# 3V3_board.net
KiCad netlist of a schematic drawn in Altium Designer
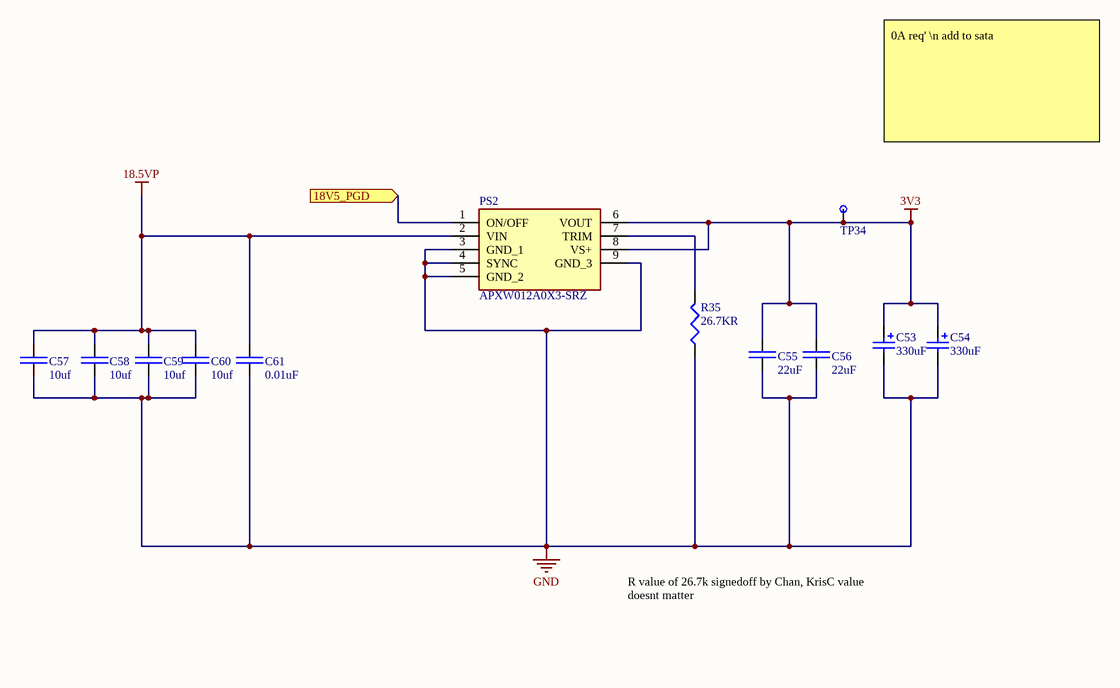
[diagram p0: 3V3_board.SchDoc]

(export (version "E")
  (design (tool "Eeschema 10.0.6"))
  (components
    (comp (ref "C53")
      (value "330uF")
      (footprint "330uF throught hole")
      (description "CAP ALUM 330UF 20% 35V RADIAL")
      (fields (field (name "TOLERANCE") "20%"))
      (libsource (lib "RSX_Capacitors") (part "35ZLH330MEFCT810X12.5"))
    )
    (comp (ref "C54")
      (value "330uF")
      (footprint "330uF throught hole")
      (description "CAP ALUM 330UF 20% 35V RADIAL")
      (fields (field (name "TOLERANCE") "20%"))
      (libsource (lib "RSX_Capacitors") (part "35ZLH330MEFCT810X12.5"))
    )
    (comp (ref "C55")
      (value "22uF")
      (footprint "22uF Capacitor")
      (description "Cap Ceramic 22uF 25V X7R 10% SMD 1210 125C Embossed T/R")
      (fields (field (name "TOLERANCE") "10%") (field (name "VOLTAGE") "25V"))
      (libsource (lib "RSX_Capacitors") (part "GRM32ER71E226KE15L"))
    )
    (comp (ref "C56")
      (value "22uF")
      (footprint "22uF Capacitor")
      (description "Cap Ceramic 22uF 25V X7R 10% SMD 1210 125C Embossed T/R")
      (fields (field (name "TOLERANCE") "10%") (field (name "VOLTAGE") "25V"))
      (libsource (lib "RSX_Capacitors") (part "GRM32ER71E226KE15L"))
    )
    (comp (ref "C57")
      (value "10uf")
      (footprint "10uF capacitor LPB")
      (description "CAP CER 10UF 50V X5R 1206")
      (fields (field (name "TOLERANCE") "20%"))
      (libsource (lib "RSX_Capacitors") (part "GRT31CR61H106ME01L"))
    )
    (comp (ref "C58")
      (value "10uf")
      (footprint "10uF capacitor LPB")
      (description "CAP CER 10UF 50V X5R 1206")
      (fields (field (name "TOLERANCE") "20%"))
      (libsource (lib "RSX_Capacitors") (part "GRT31CR61H106ME01L"))
    )
    (comp (ref "C59")
      (value "10uf")
      (footprint "10uF capacitor LPB")
      (description "CAP CER 10UF 50V X5R 1206")
      (fields (field (name "TOLERANCE") "20%"))
      (libsource (lib "RSX_Capacitors") (part "GRT31CR61H106ME01L"))
    )
    (comp (ref "C60")
      (value "10uf")
      (footprint "10uF capacitor LPB")
      (description "CAP CER 10UF 50V X5R 1206")
      (fields (field (name "TOLERANCE") "20%"))
      (libsource (lib "RSX_Capacitors") (part "GRT31CR61H106ME01L"))
    )
    (comp (ref "C61")
      (value "0.01uF")
      (footprint "0.01uF capacitor")
      (description "Cap Ceramic 0.01uF 250V X7R 10% Pad SMD 0603 125C Automotive T/R")
      (fields (field (name "TOLERANCE") "10%"))
      (libsource (lib "RSX_Capacitors") (part "C0603C103KARACAUTO"))
    )
    (comp (ref "PS2")
      (value "APXW012A0X3-SRZ")
      (footprint "SamacSys:APXW012A0X3SRZ")
      (description "Power Supply")
      (fields (field (name "MOUSER PART NUMBER") "894-APXW012A0X3-SRZ"))
      (libsource (lib "SamacSys") (part "APXW012A0X3-SRZ"))
    )
    (comp (ref "R35")
      (value "26.7KR")
      (footprint "26.7KR Resistor")
      (description "RES SMD 26.7KOHM 0.1% 1/10W 0603")
      (fields (field (name "TOLERANCE") "0.1%"))
      (libsource (lib "RSX_Resistors") (part "ERA-3AEB2672V"))
    )
    (comp (ref "TP34")
      (value "TestPt")
      (footprint "50_MIL_PAD")
      (libsource (lib "RSX_Test_Points") (part "TestPt"))
    )
  )
  (nets
    (net (code "1") (name "/18V5_PGD") (class "Default")
      (node (ref "PS2") (pin "1") (pinfunction "ON/OFF_1") (pintype "passive"))
    )
    (net (code "2") (name "3V3") (class "Default")
      (node (ref "C53") (pin "1") (pinfunction "1_1") (pintype "passive"))
      (node (ref "C54") (pin "1") (pinfunction "1_1") (pintype "passive"))
      (node (ref "C55") (pin "2") (pinfunction "16_2") (pintype "passive"))
      (node (ref "C56") (pin "2") (pinfunction "16_2") (pintype "passive"))
      (node (ref "PS2") (pin "6") (pinfunction "VOUT_6") (pintype "passive"))
      (node (ref "PS2") (pin "8") (pinfunction "VS+_8") (pintype "passive"))
      (node (ref "TP34") (pin "1") (pinfunction "1_1") (pintype "passive"))
    )
    (net (code "3") (name "18.5VP") (class "Default")
      (node (ref "C57") (pin "2") (pinfunction "16_2") (pintype "passive"))
      (node (ref "C58") (pin "2") (pinfunction "16_2") (pintype "passive"))
      (node (ref "C59") (pin "2") (pinfunction "16_2") (pintype "passive"))
      (node (ref "C60") (pin "2") (pinfunction "16_2") (pintype "passive"))
      (node (ref "C61") (pin "2") (pinfunction "16_2") (pintype "passive"))
      (node (ref "PS2") (pin "2") (pinfunction "VIN_2") (pintype "passive"))
    )
    (net (code "4") (name "GND") (class "Default")
      (node (ref "C53") (pin "2") (pinfunction "2_2") (pintype "passive"))
      (node (ref "C54") (pin "2") (pinfunction "2_2") (pintype "passive"))
      (node (ref "C55") (pin "1") (pinfunction "15_1") (pintype "passive"))
      (node (ref "C56") (pin "1") (pinfunction "15_1") (pintype "passive"))
      (node (ref "C57") (pin "1") (pinfunction "15_1") (pintype "passive"))
      (node (ref "C58") (pin "1") (pinfunction "15_1") (pintype "passive"))
      (node (ref "C59") (pin "1") (pinfunction "15_1") (pintype "passive"))
      (node (ref "C60") (pin "1") (pinfunction "15_1") (pintype "passive"))
      (node (ref "C61") (pin "1") (pinfunction "15_1") (pintype "passive"))
      (node (ref "PS2") (pin "3") (pinfunction "GND_1_3") (pintype "passive"))
      (node (ref "PS2") (pin "4") (pinfunction "SYNC_4") (pintype "passive"))
      (node (ref "PS2") (pin "5") (pinfunction "GND_2_5") (pintype "passive"))
      (node (ref "PS2") (pin "9") (pinfunction "GND_3_9") (pintype "passive"))
      (node (ref "R35") (pin "1") (pinfunction "11_1") (pintype "passive"))
    )
    (net (code "5") (name "Net-(PS2-TRIM)") (class "Default")
      (node (ref "PS2") (pin "7") (pinfunction "TRIM_7") (pintype "passive"))
      (node (ref "R35") (pin "2") (pinfunction "12_2") (pintype "passive"))
    )
  )
)
